# Processor.net
KiCad netlist of a schematic drawn in Altium Designer
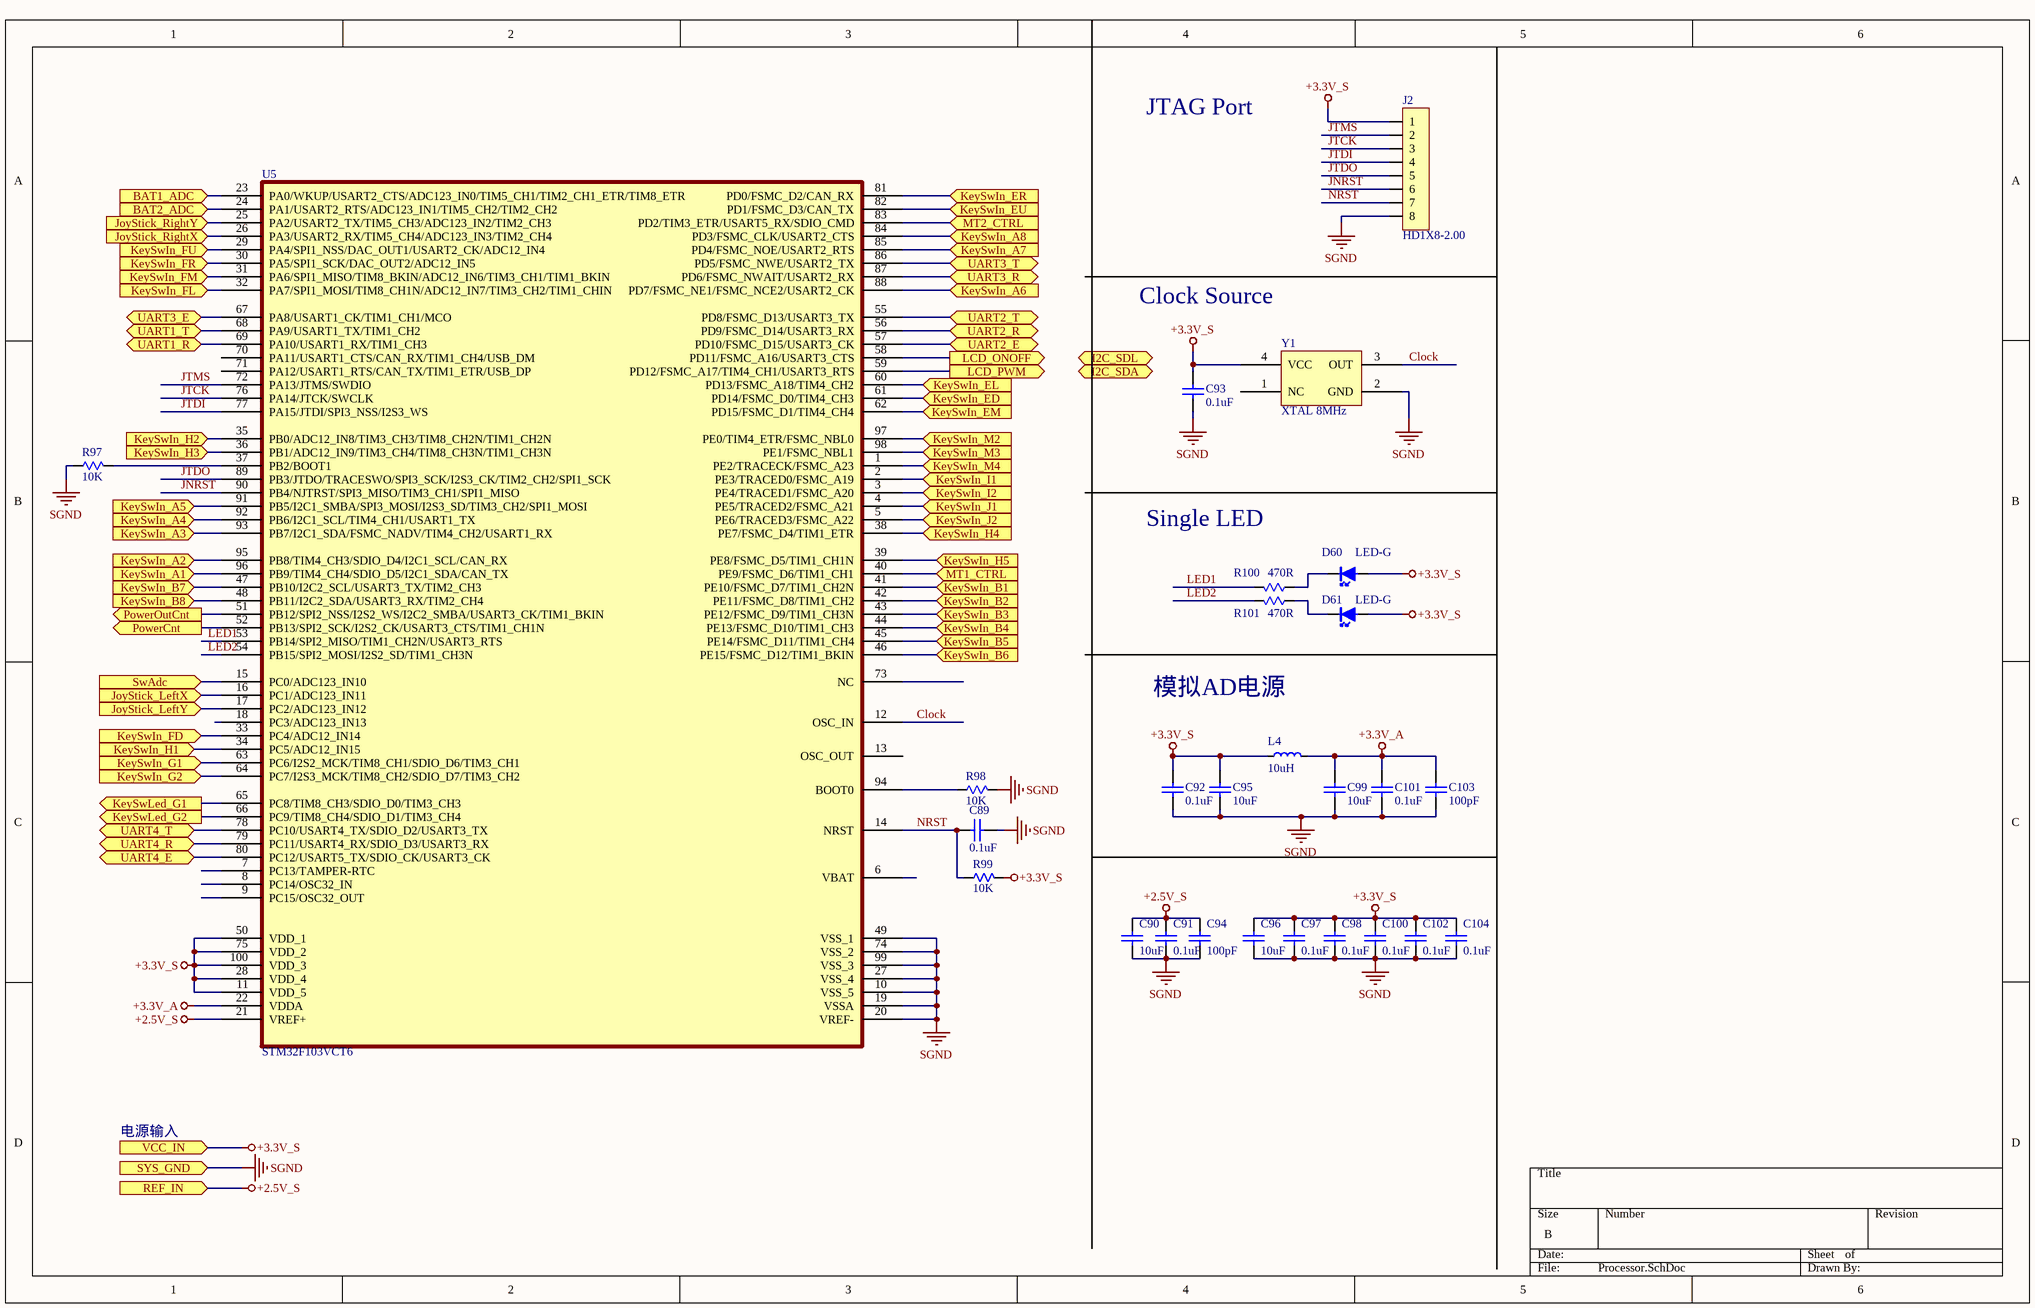
[diagram p0: Processor.SchDoc]

(export (version "E")
  (design (tool "Eeschema 10.0.6"))
  (components
    (comp (ref "C89")
      (value "0.1uF")
      (footprint "C0603")
      (description "CAP")
      (fields (field (name "PUBLISHER") "Altium Limited"))
      (libsource (lib "Passive Components Class") (part "CAP"))
    )
    (comp (ref "C90")
      (value "10uF")
      (footprint "C0805")
      (description "CAP")
      (fields (field (name "PUBLISHER") "Altium Limited"))
      (libsource (lib "Passive Components Class") (part "CAP"))
    )
    (comp (ref "C91")
      (value "0.1uF")
      (footprint "C0603")
      (description "CAP")
      (fields (field (name "PUBLISHER") "Altium Limited"))
      (libsource (lib "Passive Components Class") (part "CAP"))
    )
    (comp (ref "C92")
      (value "0.1uF")
      (footprint "C0603")
      (description "CAP")
      (fields (field (name "PUBLISHER") "Altium Limited"))
      (libsource (lib "Passive Components Class") (part "CAP"))
    )
    (comp (ref "C93")
      (value "0.1uF")
      (footprint "C0603")
      (description "Capacitor")
      (fields (field (name "PUBLISHER") "Altium Limited"))
      (libsource (lib "Miscellaneous Devices") (part "Cap"))
    )
    (comp (ref "C94")
      (value "100pF")
      (footprint "C0603")
      (description "CAP")
      (fields (field (name "PUBLISHER") "Altium Limited"))
      (libsource (lib "Passive Components Class") (part "CAP"))
    )
    (comp (ref "C95")
      (value "10uF")
      (footprint "C0805")
      (description "CAP")
      (fields (field (name "PUBLISHER") "Altium Limited"))
      (libsource (lib "Passive Components Class") (part "CAP"))
    )
    (comp (ref "C96")
      (value "10uF")
      (footprint "C0805")
      (description "CAP")
      (fields (field (name "PUBLISHER") "Altium Limited"))
      (libsource (lib "Passive Components Class") (part "CAP"))
    )
    (comp (ref "C97")
      (value "0.1uF")
      (footprint "C0603")
      (description "CAP")
      (fields (field (name "PUBLISHER") "Altium Limited"))
      (libsource (lib "Passive Components Class") (part "CAP"))
    )
    (comp (ref "C98")
      (value "0.1uF")
      (footprint "C0603")
      (description "CAP")
      (fields (field (name "PUBLISHER") "Altium Limited"))
      (libsource (lib "Passive Components Class") (part "CAP"))
    )
    (comp (ref "C99")
      (value "10uF")
      (footprint "C0805")
      (description "CAP")
      (fields (field (name "PUBLISHER") "Altium Limited"))
      (libsource (lib "Passive Components Class") (part "CAP"))
    )
    (comp (ref "C100")
      (value "0.1uF")
      (footprint "C0603")
      (description "CAP")
      (fields (field (name "PUBLISHER") "Altium Limited"))
      (libsource (lib "Passive Components Class") (part "CAP"))
    )
    (comp (ref "C101")
      (value "0.1uF")
      (footprint "C0603")
      (description "CAP")
      (fields (field (name "PUBLISHER") "Altium Limited"))
      (libsource (lib "Passive Components Class") (part "CAP"))
    )
    (comp (ref "C102")
      (value "0.1uF")
      (footprint "C0603")
      (description "CAP")
      (fields (field (name "PUBLISHER") "Altium Limited"))
      (libsource (lib "Passive Components Class") (part "CAP"))
    )
    (comp (ref "C103")
      (value "100pF")
      (footprint "C0603")
      (description "CAP")
      (fields (field (name "PUBLISHER") "Altium Limited"))
      (libsource (lib "Passive Components Class") (part "CAP"))
    )
    (comp (ref "C104")
      (value "0.1uF")
      (footprint "C0603")
      (description "CAP")
      (fields (field (name "PUBLISHER") "Altium Limited"))
      (libsource (lib "Passive Components Class") (part "CAP"))
    )
    (comp (ref "D60")
      (value "LED-G")
      (footprint "LED0805")
      (libsource (lib "Passive Components Class") (part "LED"))
    )
    (comp (ref "D61")
      (value "LED-G")
      (footprint "LED0805")
      (libsource (lib "Passive Components Class") (part "LED"))
    )
    (comp (ref "J2")
      (value "HD1X8-2.00")
      (footprint "SHD1X8-2.00")
      (libsource (lib "Connector Class") (part "HEADER1X8"))
    )
    (comp (ref "L4")
      (value "10uH")
      (footprint "L0603-C")
      (description "INDUCTOR")
      (fields (field (name "PUBLISHER") "Altium Limited"))
      (libsource (lib "Passive Components Class") (part "INDUCTOR"))
    )
    (comp (ref "R97")
      (value "10K")
      (footprint "R0603")
      (description "Resistor")
      (fields (field (name "PUBLISHER") "Altium Limited"))
      (libsource (lib "UP-Robot") (part "Res"))
    )
    (comp (ref "R98")
      (value "10K")
      (footprint "R0603")
      (description "Resistor")
      (fields (field (name "PUBLISHER") "Altium Limited"))
      (libsource (lib "UP-Robot") (part "Res"))
    )
    (comp (ref "R99")
      (value "10K")
      (footprint "R0603")
      (description "Resistor")
      (fields (field (name "PUBLISHER") "Altium Limited"))
      (libsource (lib "UP-Robot") (part "Res"))
    )
    (comp (ref "R100")
      (value "470R")
      (footprint "R0805")
      (description "Resistor")
      (fields (field (name "PUBLISHER") "Altium Limited"))
      (libsource (lib "UP-Robot") (part "Res"))
    )
    (comp (ref "R101")
      (value "470R")
      (footprint "R0805")
      (description "Resistor")
      (fields (field (name "PUBLISHER") "Altium Limited"))
      (libsource (lib "UP-Robot") (part "Res"))
    )
    (comp (ref "U5")
      (value "STM32F103VCT6")
      (footprint "STM32F103VCT6")
      (libsource (lib "Microcontrollers Class") (part "STM32F103VCT6"))
    )
    (comp (ref "Y1")
      (value "XTAL 8MHz")
      (footprint "XTAL 5.0X7.0-SM")
      (libsource (lib "Mic2805") (part "XTAL"))
    )
  )
  (nets
    (net (code "1") (name "+2.5V_S") (class "Default")
      (node (ref "C90") (pin "1") (pinfunction "1_1") (pintype "passive"))
      (node (ref "C91") (pin "1") (pinfunction "1_1") (pintype "passive"))
      (node (ref "C94") (pin "1") (pinfunction "1_1") (pintype "passive"))
      (node (ref "U5") (pin "21") (pinfunction "VREF+_21") (pintype "passive"))
    )
    (net (code "2") (name "+3.3V_A") (class "Default")
      (node (ref "C101") (pin "2") (pinfunction "2_2") (pintype "passive"))
      (node (ref "C103") (pin "2") (pinfunction "2_2") (pintype "passive"))
      (node (ref "C99") (pin "2") (pinfunction "2_2") (pintype "passive"))
      (node (ref "L4") (pin "2") (pinfunction "2_2") (pintype "passive"))
      (node (ref "U5") (pin "22") (pinfunction "VDDA_22") (pintype "passive"))
    )
    (net (code "3") (name "+3.3V_S") (class "Default")
      (node (ref "C100") (pin "1") (pinfunction "1_1") (pintype "passive"))
      (node (ref "C102") (pin "1") (pinfunction "1_1") (pintype "passive"))
      (node (ref "C104") (pin "1") (pinfunction "1_1") (pintype "passive"))
      (node (ref "C92") (pin "2") (pinfunction "2_2") (pintype "passive"))
      (node (ref "C93") (pin "2") (pinfunction "2_2") (pintype "passive"))
      (node (ref "C95") (pin "2") (pinfunction "2_2") (pintype "passive"))
      (node (ref "C96") (pin "1") (pinfunction "1_1") (pintype "passive"))
      (node (ref "C97") (pin "1") (pinfunction "1_1") (pintype "passive"))
      (node (ref "C98") (pin "1") (pinfunction "1_1") (pintype "passive"))
      (node (ref "D60") (pin "1") (pinfunction "A_1") (pintype "passive"))
      (node (ref "D61") (pin "1") (pinfunction "A_1") (pintype "passive"))
      (node (ref "J2") (pin "1") (pinfunction "1_1") (pintype "passive"))
      (node (ref "L4") (pin "1") (pinfunction "1_1") (pintype "passive"))
      (node (ref "R99") (pin "1") (pinfunction "1_1") (pintype "passive"))
      (node (ref "U5") (pin "100") (pinfunction "VDD_3_100") (pintype "passive"))
      (node (ref "U5") (pin "11") (pinfunction "VDD_5_11") (pintype "passive"))
      (node (ref "U5") (pin "28") (pinfunction "VDD_4_28") (pintype "passive"))
      (node (ref "U5") (pin "50") (pinfunction "VDD_1_50") (pintype "passive"))
      (node (ref "U5") (pin "75") (pinfunction "VDD_2_75") (pintype "passive"))
      (node (ref "Y1") (pin "4") (pinfunction "VCC_4") (pintype "passive"))
    )
    (net (code "4") (name "/BAT1_ADC") (class "Default")
      (node (ref "U5") (pin "23") (pinfunction "PA0/WKUP/USART2_CTS/ADC123_IN0/TIM5_CH1/TIM2_CH1_ETR/TIM8_ETR_23") (pintype "passive"))
    )
    (net (code "5") (name "/BAT2_ADC") (class "Default")
      (node (ref "U5") (pin "24") (pinfunction "PA1/USART2_RTS/ADC123_IN1/TIM5_CH2/TIM2_CH2_24") (pintype "passive"))
    )
    (net (code "6") (name "/Clock") (class "Default")
      (node (ref "U5") (pin "12") (pinfunction "OSC_IN_12") (pintype "passive"))
      (node (ref "Y1") (pin "3") (pinfunction "OUT_3") (pintype "passive"))
    )
    (net (code "9") (name "/JNRST") (class "Default")
      (node (ref "J2") (pin "6") (pinfunction "6_6") (pintype "passive"))
      (node (ref "U5") (pin "90") (pinfunction "PB4/NJTRST/SPI3_MISO/TIM3_CH1/SPI1_MISO_90") (pintype "passive"))
    )
    (net (code "10") (name "/JTCK") (class "Default")
      (node (ref "J2") (pin "3") (pinfunction "3_3") (pintype "passive"))
      (node (ref "U5") (pin "76") (pinfunction "PA14/JTCK/SWCLK_76") (pintype "passive"))
    )
    (net (code "11") (name "/JTDI") (class "Default")
      (node (ref "J2") (pin "4") (pinfunction "4_4") (pintype "passive"))
      (node (ref "U5") (pin "77") (pinfunction "PA15/JTDI/SPI3_NSS/I2S3_WS_77") (pintype "passive"))
    )
    (net (code "12") (name "/JTDO") (class "Default")
      (node (ref "J2") (pin "5") (pinfunction "5_5") (pintype "passive"))
      (node (ref "U5") (pin "89") (pinfunction "PB3/JTDO/TRACESWO/SPI3_SCK/I2S3_CK/TIM2_CH2/SPI1_SCK_89") (pintype "passive"))
    )
    (net (code "13") (name "/JTMS") (class "Default")
      (node (ref "J2") (pin "2") (pinfunction "2_2") (pintype "passive"))
      (node (ref "U5") (pin "72") (pinfunction "PA13/JTMS/SWDIO_72") (pintype "passive"))
    )
    (net (code "14") (name "/JoyStick_LeftX") (class "Default")
      (node (ref "U5") (pin "16") (pinfunction "PC1/ADC123_IN11_16") (pintype "passive"))
    )
    (net (code "15") (name "/JoyStick_LeftY") (class "Default")
      (node (ref "U5") (pin "17") (pinfunction "PC2/ADC123_IN12_17") (pintype "passive"))
    )
    (net (code "16") (name "/JoyStick_RightX") (class "Default")
      (node (ref "U5") (pin "26") (pinfunction "PA3/USART2_RX/TIM5_CH4/ADC123_IN3/TIM2_CH4_26") (pintype "passive"))
    )
    (net (code "17") (name "/JoyStick_RightY") (class "Default")
      (node (ref "U5") (pin "25") (pinfunction "PA2/USART2_TX/TIM5_CH3/ADC123_IN2/TIM2_CH3_25") (pintype "passive"))
    )
    (net (code "18") (name "/KeySwIn_A1") (class "Default")
      (node (ref "U5") (pin "96") (pinfunction "PB9/TIM4_CH4/SDIO_D5/I2C1_SDA/CAN_TX_96") (pintype "passive"))
    )
    (net (code "19") (name "/KeySwIn_A2") (class "Default")
      (node (ref "U5") (pin "95") (pinfunction "PB8/TIM4_CH3/SDIO_D4/I2C1_SCL/CAN_RX_95") (pintype "passive"))
    )
    (net (code "20") (name "/KeySwIn_A3") (class "Default")
      (node (ref "U5") (pin "93") (pinfunction "PB7/I2C1_SDA/FSMC_NADV/TIM4_CH2/USART1_RX_93") (pintype "passive"))
    )
    (net (code "21") (name "/KeySwIn_A4") (class "Default")
      (node (ref "U5") (pin "92") (pinfunction "PB6/I2C1_SCL/TIM4_CH1/USART1_TX_92") (pintype "passive"))
    )
    (net (code "22") (name "/KeySwIn_A5") (class "Default")
      (node (ref "U5") (pin "91") (pinfunction "PB5/I2C1_SMBA/SPI3_MOSI/I2S3_SD/TIM3_CH2/SPI1_MOSI_91") (pintype "passive"))
    )
    (net (code "23") (name "/KeySwIn_A6") (class "Default")
      (node (ref "U5") (pin "88") (pinfunction "PD7/FSMC_NE1/FSMC_NCE2/USART2_CK_88") (pintype "passive"))
    )
    (net (code "24") (name "/KeySwIn_A7") (class "Default")
      (node (ref "U5") (pin "85") (pinfunction "PD4/FSMC_NOE/USART2_RTS_85") (pintype "passive"))
    )
    (net (code "25") (name "/KeySwIn_A8") (class "Default")
      (node (ref "U5") (pin "84") (pinfunction "PD3/FSMC_CLK/USART2_CTS_84") (pintype "passive"))
    )
    (net (code "26") (name "/KeySwIn_B1") (class "Default")
      (node (ref "U5") (pin "41") (pinfunction "PE10/FSMC_D7/TIM1_CH2N_41") (pintype "passive"))
    )
    (net (code "27") (name "/KeySwIn_B2") (class "Default")
      (node (ref "U5") (pin "42") (pinfunction "PE11/FSMC_D8/TIM1_CH2_42") (pintype "passive"))
    )
    (net (code "28") (name "/KeySwIn_B3") (class "Default")
      (node (ref "U5") (pin "43") (pinfunction "PE12/FSMC_D9/TIM1_CH3N_43") (pintype "passive"))
    )
    (net (code "29") (name "/KeySwIn_B4") (class "Default")
      (node (ref "U5") (pin "44") (pinfunction "PE13/FSMC_D10/TIM1_CH3_44") (pintype "passive"))
    )
    (net (code "30") (name "/KeySwIn_B5") (class "Default")
      (node (ref "U5") (pin "45") (pinfunction "PE14/FSMC_D11/TIM1_CH4_45") (pintype "passive"))
    )
    (net (code "31") (name "/KeySwIn_B6") (class "Default")
      (node (ref "U5") (pin "46") (pinfunction "PE15/FSMC_D12/TIM1_BKIN_46") (pintype "passive"))
    )
    (net (code "32") (name "/KeySwIn_B7") (class "Default")
      (node (ref "U5") (pin "47") (pinfunction "PB10/I2C2_SCL/USART3_TX/TIM2_CH3_47") (pintype "passive"))
    )
    (net (code "33") (name "/KeySwIn_B8") (class "Default")
      (node (ref "U5") (pin "48") (pinfunction "PB11/I2C2_SDA/USART3_RX/TIM2_CH4_48") (pintype "passive"))
    )
    (net (code "34") (name "/KeySwIn_ED") (class "Default")
      (node (ref "U5") (pin "61") (pinfunction "PD14/FSMC_D0/TIM4_CH3_61") (pintype "passive"))
    )
    (net (code "35") (name "/KeySwIn_EL") (class "Default")
      (node (ref "U5") (pin "60") (pinfunction "PD13/FSMC_A18/TIM4_CH2_60") (pintype "passive"))
    )
    (net (code "36") (name "/KeySwIn_EM") (class "Default")
      (node (ref "U5") (pin "62") (pinfunction "PD15/FSMC_D1/TIM4_CH4_62") (pintype "passive"))
    )
    (net (code "37") (name "/KeySwIn_ER") (class "Default")
      (node (ref "U5") (pin "81") (pinfunction "PD0/FSMC_D2/CAN_RX_81") (pintype "passive"))
    )
    (net (code "38") (name "/KeySwIn_EU") (class "Default")
      (node (ref "U5") (pin "82") (pinfunction "PD1/FSMC_D3/CAN_TX_82") (pintype "passive"))
    )
    (net (code "39") (name "/KeySwIn_FD") (class "Default")
      (node (ref "U5") (pin "33") (pinfunction "PC4/ADC12_IN14_33") (pintype "passive"))
    )
    (net (code "40") (name "/KeySwIn_FL") (class "Default")
      (node (ref "U5") (pin "32") (pinfunction "PA7/SPI1_MOSI/TIM8_CH1N/ADC12_IN7/TIM3_CH2/TIM1_CHIN_32") (pintype "passive"))
    )
    (net (code "41") (name "/KeySwIn_FM") (class "Default")
      (node (ref "U5") (pin "31") (pinfunction "PA6/SPI1_MISO/TIM8_BKIN/ADC12_IN6/TIM3_CH1/TIM1_BKIN_31") (pintype "passive"))
    )
    (net (code "42") (name "/KeySwIn_FR") (class "Default")
      (node (ref "U5") (pin "30") (pinfunction "PA5/SPI1_SCK/DAC_OUT2/ADC12_IN5_30") (pintype "passive"))
    )
    (net (code "43") (name "/KeySwIn_FU") (class "Default")
      (node (ref "U5") (pin "29") (pinfunction "PA4/SPI1_NSS/DAC_OUT1/USART2_CK/ADC12_IN4_29") (pintype "passive"))
    )
    (net (code "44") (name "/KeySwIn_G1") (class "Default")
      (node (ref "U5") (pin "63") (pinfunction "PC6/I2S2_MCK/TIM8_CH1/SDIO_D6/TIM3_CH1_63") (pintype "passive"))
    )
    (net (code "45") (name "/KeySwIn_G2") (class "Default")
      (node (ref "U5") (pin "64") (pinfunction "PC7/I2S3_MCK/TIM8_CH2/SDIO_D7/TIM3_CH2_64") (pintype "passive"))
    )
    (net (code "46") (name "/KeySwIn_H1") (class "Default")
      (node (ref "U5") (pin "34") (pinfunction "PC5/ADC12_IN15_34") (pintype "passive"))
    )
    (net (code "47") (name "/KeySwIn_H2") (class "Default")
      (node (ref "U5") (pin "35") (pinfunction "PB0/ADC12_IN8/TIM3_CH3/TIM8_CH2N/TIM1_CH2N_35") (pintype "passive"))
    )
    (net (code "48") (name "/KeySwIn_H3") (class "Default")
      (node (ref "U5") (pin "36") (pinfunction "PB1/ADC12_IN9/TIM3_CH4/TIM8_CH3N/TIM1_CH3N_36") (pintype "passive"))
    )
    (net (code "49") (name "/KeySwIn_H4") (class "Default")
      (node (ref "U5") (pin "38") (pinfunction "PE7/FSMC_D4/TIM1_ETR_38") (pintype "passive"))
    )
    (net (code "50") (name "/KeySwIn_H5") (class "Default")
      (node (ref "U5") (pin "39") (pinfunction "PE8/FSMC_D5/TIM1_CH1N_39") (pintype "passive"))
    )
    (net (code "51") (name "/KeySwIn_I1") (class "Default")
      (node (ref "U5") (pin "2") (pinfunction "PE3/TRACED0/FSMC_A19_2") (pintype "passive"))
    )
    (net (code "52") (name "/KeySwIn_I2") (class "Default")
      (node (ref "U5") (pin "3") (pinfunction "PE4/TRACED1/FSMC_A20_3") (pintype "passive"))
    )
    (net (code "53") (name "/KeySwIn_J1") (class "Default")
      (node (ref "U5") (pin "4") (pinfunction "PE5/TRACED2/FSMC_A21_4") (pintype "passive"))
    )
    (net (code "54") (name "/KeySwIn_J2") (class "Default")
      (node (ref "U5") (pin "5") (pinfunction "PE6/TRACED3/FSMC_A22_5") (pintype "passive"))
    )
    (net (code "55") (name "/KeySwIn_M2") (class "Default")
      (node (ref "U5") (pin "97") (pinfunction "PE0/TIM4_ETR/FSMC_NBL0_97") (pintype "passive"))
    )
    (net (code "56") (name "/KeySwIn_M3") (class "Default")
      (node (ref "U5") (pin "98") (pinfunction "PE1/FSMC_NBL1_98") (pintype "passive"))
    )
    (net (code "57") (name "/KeySwIn_M4") (class "Default")
      (node (ref "U5") (pin "1") (pinfunction "PE2/TRACECK/FSMC_A23_1") (pintype "passive"))
    )
    (net (code "58") (name "/KeySwLed_G1") (class "Default")
      (node (ref "U5") (pin "65") (pinfunction "PC8/TIM8_CH3/SDIO_D0/TIM3_CH3_65") (pintype "passive"))
    )
    (net (code "59") (name "/KeySwLed_G2") (class "Default")
      (node (ref "U5") (pin "66") (pinfunction "PC9/TIM8_CH4/SDIO_D1/TIM3_CH4_66") (pintype "passive"))
    )
    (net (code "60") (name "/LCD_ONOFF") (class "Default")
      (node (ref "U5") (pin "58") (pinfunction "PD11/FSMC_A16/USART3_CTS_58") (pintype "passive"))
    )
    (net (code "61") (name "/LCD_PWM") (class "Default")
      (node (ref "U5") (pin "59") (pinfunction "PD12/FSMC_A17/TIM4_CH1/USART3_RTS_59") (pintype "passive"))
    )
    (net (code "62") (name "/LED1") (class "Default")
      (node (ref "R100") (pin "1") (pinfunction "1_1") (pintype "passive"))
      (node (ref "U5") (pin "53") (pinfunction "PB14/SPI2_MISO/TIM1_CH2N/USART3_RTS_53") (pintype "passive"))
    )
    (net (code "63") (name "/LED2") (class "Default")
      (node (ref "R101") (pin "1") (pinfunction "1_1") (pintype "passive"))
      (node (ref "U5") (pin "54") (pinfunction "PB15/SPI2_MOSI/I2S2_SD/TIM1_CH3N_54") (pintype "passive"))
    )
    (net (code "64") (name "/MT1_CTRL") (class "Default")
      (node (ref "U5") (pin "40") (pinfunction "PE9/FSMC_D6/TIM1_CH1_40") (pintype "passive"))
    )
    (net (code "65") (name "/MT2_CTRL") (class "Default")
      (node (ref "U5") (pin "83") (pinfunction "PD2/TIM3_ETR/USART5_RX/SDIO_CMD_83") (pintype "passive"))
    )
    (net (code "66") (name "/NRST") (class "Default")
      (node (ref "C89") (pin "1") (pinfunction "1_1") (pintype "passive"))
      (node (ref "J2") (pin "7") (pinfunction "7_7") (pintype "passive"))
      (node (ref "R99") (pin "2") (pinfunction "2_2") (pintype "passive"))
      (node (ref "U5") (pin "14") (pinfunction "NRST_14") (pintype "passive"))
    )
    (net (code "67") (name "/PowerCnt") (class "Default")
      (node (ref "U5") (pin "52") (pinfunction "PB13/SPI2_SCK/I2S2_CK/USART3_CTS/TIM1_CH1N_52") (pintype "passive"))
    )
    (net (code "68") (name "/PowerOutCnt") (class "Default")
      (node (ref "U5") (pin "51") (pinfunction "PB12/SPI2_NSS/I2S2_WS/I2C2_SMBA/USART3_CK/TIM1_BKIN_51") (pintype "passive"))
    )
    (net (code "69") (name "/SwAdc") (class "Default")
      (node (ref "U5") (pin "15") (pinfunction "PC0/ADC123_IN10_15") (pintype "passive"))
    )
    (net (code "70") (name "/UART1_R") (class "Default")
      (node (ref "U5") (pin "69") (pinfunction "PA10/USART1_RX/TIM1_CH3_69") (pintype "passive"))
    )
    (net (code "71") (name "/UART1_T") (class "Default")
      (node (ref "U5") (pin "68") (pinfunction "PA9/USART1_TX/TIM1_CH2_68") (pintype "passive"))
    )
    (net (code "72") (name "/UART2_E") (class "Default")
      (node (ref "U5") (pin "57") (pinfunction "PD10/FSMC_D15/USART3_CK_57") (pintype "passive"))
    )
    (net (code "73") (name "/UART2_R") (class "Default")
      (node (ref "U5") (pin "56") (pinfunction "PD9/FSMC_D14/USART3_RX_56") (pintype "passive"))
    )
    (net (code "74") (name "/UART2_T") (class "Default")
      (node (ref "U5") (pin "55") (pinfunction "PD8/FSMC_D13/USART3_TX_55") (pintype "passive"))
    )
    (net (code "75") (name "/UART3_E") (class "Default")
      (node (ref "U5") (pin "67") (pinfunction "PA8/USART1_CK/TIM1_CH1/MCO_67") (pintype "passive"))
    )
    (net (code "76") (name "/UART3_R") (class "Default")
      (node (ref "U5") (pin "87") (pinfunction "PD6/FSMC_NWAIT/USART2_RX_87") (pintype "passive"))
    )
    (net (code "77") (name "/UART3_T") (class "Default")
      (node (ref "U5") (pin "86") (pinfunction "PD5/FSMC_NWE/USART2_TX_86") (pintype "passive"))
    )
    (net (code "78") (name "/UART4_E") (class "Default")
      (node (ref "U5") (pin "80") (pinfunction "PC12/USART5_TX/SDIO_CK/USART3_CK_80") (pintype "passive"))
    )
    (net (code "79") (name "/UART4_R") (class "Default")
      (node (ref "U5") (pin "79") (pinfunction "PC11/USART4_RX/SDIO_D3/USART3_RX_79") (pintype "passive"))
    )
    (net (code "80") (name "/UART4_T") (class "Default")
      (node (ref "U5") (pin "78") (pinfunction "PC10/USART4_TX/SDIO_D2/USART3_TX_78") (pintype "passive"))
    )
    (net (code "81") (name "Net-(D60-K)") (class "Default")
      (node (ref "D60") (pin "2") (pinfunction "K_2") (pintype "passive"))
      (node (ref "R100") (pin "2") (pinfunction "2_2") (pintype "passive"))
    )
    (net (code "82") (name "Net-(D61-K)") (class "Default")
      (node (ref "D61") (pin "2") (pinfunction "K_2") (pintype "passive"))
      (node (ref "R101") (pin "2") (pinfunction "2_2") (pintype "passive"))
    )
    (net (code "83") (name "Net-(U5-BOOT0)") (class "Default")
      (node (ref "R98") (pin "2") (pinfunction "2_2") (pintype "passive"))
      (node (ref "U5") (pin "94") (pinfunction "BOOT0_94") (pintype "passive"))
    )
    (net (code "84") (name "Net-(U5-PB2{slash}BOOT1)") (class "Default")
      (node (ref "R97") (pin "1") (pinfunction "1_1") (pintype "passive"))
      (node (ref "U5") (pin "37") (pinfunction "PB2/BOOT1_37") (pintype "passive"))
    )
    (net (code "85") (name "SGND") (class "Default")
      (node (ref "C100") (pin "2") (pinfunction "2_2") (pintype "passive"))
      (node (ref "C101") (pin "1") (pinfunction "1_1") (pintype "passive"))
      (node (ref "C102") (pin "2") (pinfunction "2_2") (pintype "passive"))
      (node (ref "C103") (pin "1") (pinfunction "1_1") (pintype "passive"))
      (node (ref "C104") (pin "2") (pinfunction "2_2") (pintype "passive"))
      (node (ref "C89") (pin "2") (pinfunction "2_2") (pintype "passive"))
      (node (ref "C90") (pin "2") (pinfunction "2_2") (pintype "passive"))
      (node (ref "C91") (pin "2") (pinfunction "2_2") (pintype "passive"))
      (node (ref "C92") (pin "1") (pinfunction "1_1") (pintype "passive"))
      (node (ref "C93") (pin "1") (pinfunction "1_1") (pintype "passive"))
      (node (ref "C94") (pin "2") (pinfunction "2_2") (pintype "passive"))
      (node (ref "C95") (pin "1") (pinfunction "1_1") (pintype "passive"))
      (node (ref "C96") (pin "2") (pinfunction "2_2") (pintype "passive"))
      (node (ref "C97") (pin "2") (pinfunction "2_2") (pintype "passive"))
      (node (ref "C98") (pin "2") (pinfunction "2_2") (pintype "passive"))
      (node (ref "C99") (pin "1") (pinfunction "1_1") (pintype "passive"))
      (node (ref "J2") (pin "8") (pinfunction "8_8") (pintype "passive"))
      (node (ref "R97") (pin "2") (pinfunction "2_2") (pintype "passive"))
      (node (ref "R98") (pin "1") (pinfunction "1_1") (pintype "passive"))
      (node (ref "U5") (pin "10") (pinfunction "VSS_5_10") (pintype "passive"))
      (node (ref "U5") (pin "19") (pinfunction "VSSA_19") (pintype "passive"))
      (node (ref "U5") (pin "20") (pinfunction "VREF-_20") (pintype "passive"))
      (node (ref "U5") (pin "27") (pinfunction "VSS_4_27") (pintype "passive"))
      (node (ref "U5") (pin "49") (pinfunction "VSS_1_49") (pintype "passive"))
      (node (ref "U5") (pin "74") (pinfunction "VSS_2_74") (pintype "passive"))
      (node (ref "U5") (pin "99") (pinfunction "VSS_3_99") (pintype "passive"))
      (node (ref "Y1") (pin "2") (pinfunction "GND_2") (pintype "passive"))
    )
    (net (code "86") (name "unconnected-(U5-NC-Pad73)") (class "Default")
      (node (ref "U5") (pin "73") (pinfunction "NC_73") (pintype "passive"))
    )
    (net (code "87") (name "unconnected-(U5-OSC_OUT-Pad13)") (class "Default")
      (node (ref "U5") (pin "13") (pinfunction "OSC_OUT_13") (pintype "passive"))
    )
    (net (code "88") (name "unconnected-(U5-PA11{slash}USART1_CTS{slash}CAN_RX{slash}TIM1_CH4{slash}USB_DM-Pad70)") (class "Default")
      (node (ref "U5") (pin "70") (pinfunction "PA11/USART1_CTS/CAN_RX/TIM1_CH4/USB_DM_70") (pintype "passive"))
    )
    (net (code "89") (name "unconnected-(U5-PA12{slash}USART1_RTS{slash}CAN_TX{slash}TIM1_ETR{slash}USB_DP-Pad71)") (class "Default")
      (node (ref "U5") (pin "71") (pinfunction "PA12/USART1_RTS/CAN_TX/TIM1_ETR/USB_DP_71") (pintype "passive"))
    )
    (net (code "90") (name "unconnected-(U5-PC3{slash}ADC123_IN13-Pad18)") (class "Default")
      (node (ref "U5") (pin "18") (pinfunction "PC3/ADC123_IN13_18") (pintype "passive"))
    )
    (net (code "91") (name "unconnected-(U5-PC13{slash}TAMPER-RTC-Pad7)") (class "Default")
      (node (ref "U5") (pin "7") (pinfunction "PC13/TAMPER-RTC_7") (pintype "passive"))
    )
    (net (code "92") (name "unconnected-(U5-PC14{slash}OSC32_IN-Pad8)") (class "Default")
      (node (ref "U5") (pin "8") (pinfunction "PC14/OSC32_IN_8") (pintype "passive"))
    )
    (net (code "93") (name "unconnected-(U5-PC15{slash}OSC32_OUT-Pad9)") (class "Default")
      (node (ref "U5") (pin "9") (pinfunction "PC15/OSC32_OUT_9") (pintype "passive"))
    )
    (net (code "94") (name "unconnected-(U5-VBAT-Pad6)") (class "Default")
      (node (ref "U5") (pin "6") (pinfunction "VBAT_6") (pintype "passive"))
    )
    (net (code "95") (name "unconnected-(Y1-NC-Pad1)") (class "Default")
      (node (ref "Y1") (pin "1") (pinfunction "NC_1") (pintype "passive"))
    )
  )
)
